# SSR_POWER_STAGE.net
KiCad netlist of a schematic drawn in Altium Designer
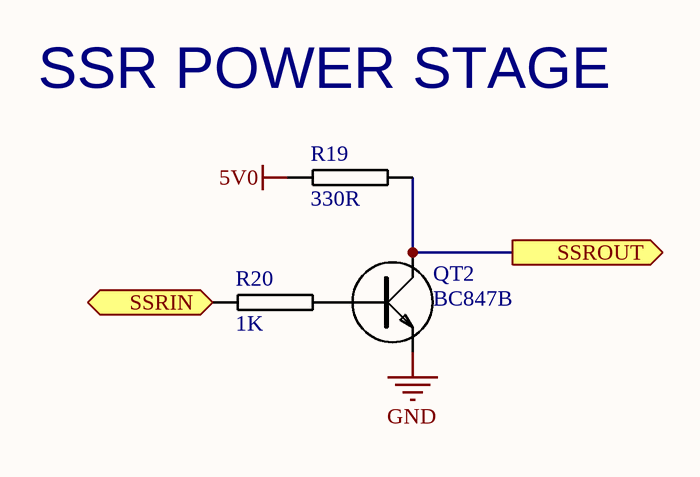
[diagram p0: SSR POWER STAGE.SchDoc]

(export (version "E")
  (design (tool "Eeschema 10.0.6"))
  (components
    (comp (ref "QT2")
      (value "BC847B")
      (footprint "SOT23-BCE")
      (description "BC847 SMALL SIGNAL NPN TRANSISTOR")
      (fields
        (field (name "MANUFACTURER PART NUMBER") "BC847BMTF")
        (field (name "MANUFACTURER") "Fairchild Semiconductor")
      )
      (libsource (lib "vh_altium_library") (part "BC847"))
    )
    (comp (ref "R19")
      (value "330R")
      (footprint "0805R-330")
      (description "RESISTOR 0805 1/4 WATT THIN FILM")
      (libsource (lib "RVA_Altium_Library") (part "0805R-330"))
    )
    (comp (ref "R20")
      (value "1K")
      (footprint "0805R-1K")
      (description "RESISTOR 0805 1/4 WATT THIN FILM")
      (libsource (lib "RVA_Altium_Library") (part "0805R-1K"))
    )
  )
  (nets
    (net (code "1") (name "/SSRIN") (class "Default") (node (ref "R20") (pin "1") (pintype "passive")))
    (net (code "2") (name "/SSROUT") (class "Default")
      (node (ref "QT2") (pin "C") (pintype "passive"))
      (node (ref "R19") (pin "2") (pintype "passive"))
    )
    (net (code "3") (name "5V0") (class "Default") (node (ref "R19") (pin "1") (pintype "passive")))
    (net (code "4") (name "GND") (class "Default") (node (ref "QT2") (pin "E") (pintype "passive")))
    (net (code "5") (name "Net-(QT2-PadB)") (class "Default")
      (node (ref "QT2") (pin "B") (pintype "passive"))
      (node (ref "R20") (pin "2") (pintype "passive"))
    )
  )
)
